# Net510.net
KiCad netlist of a schematic drawn in Altium Designer
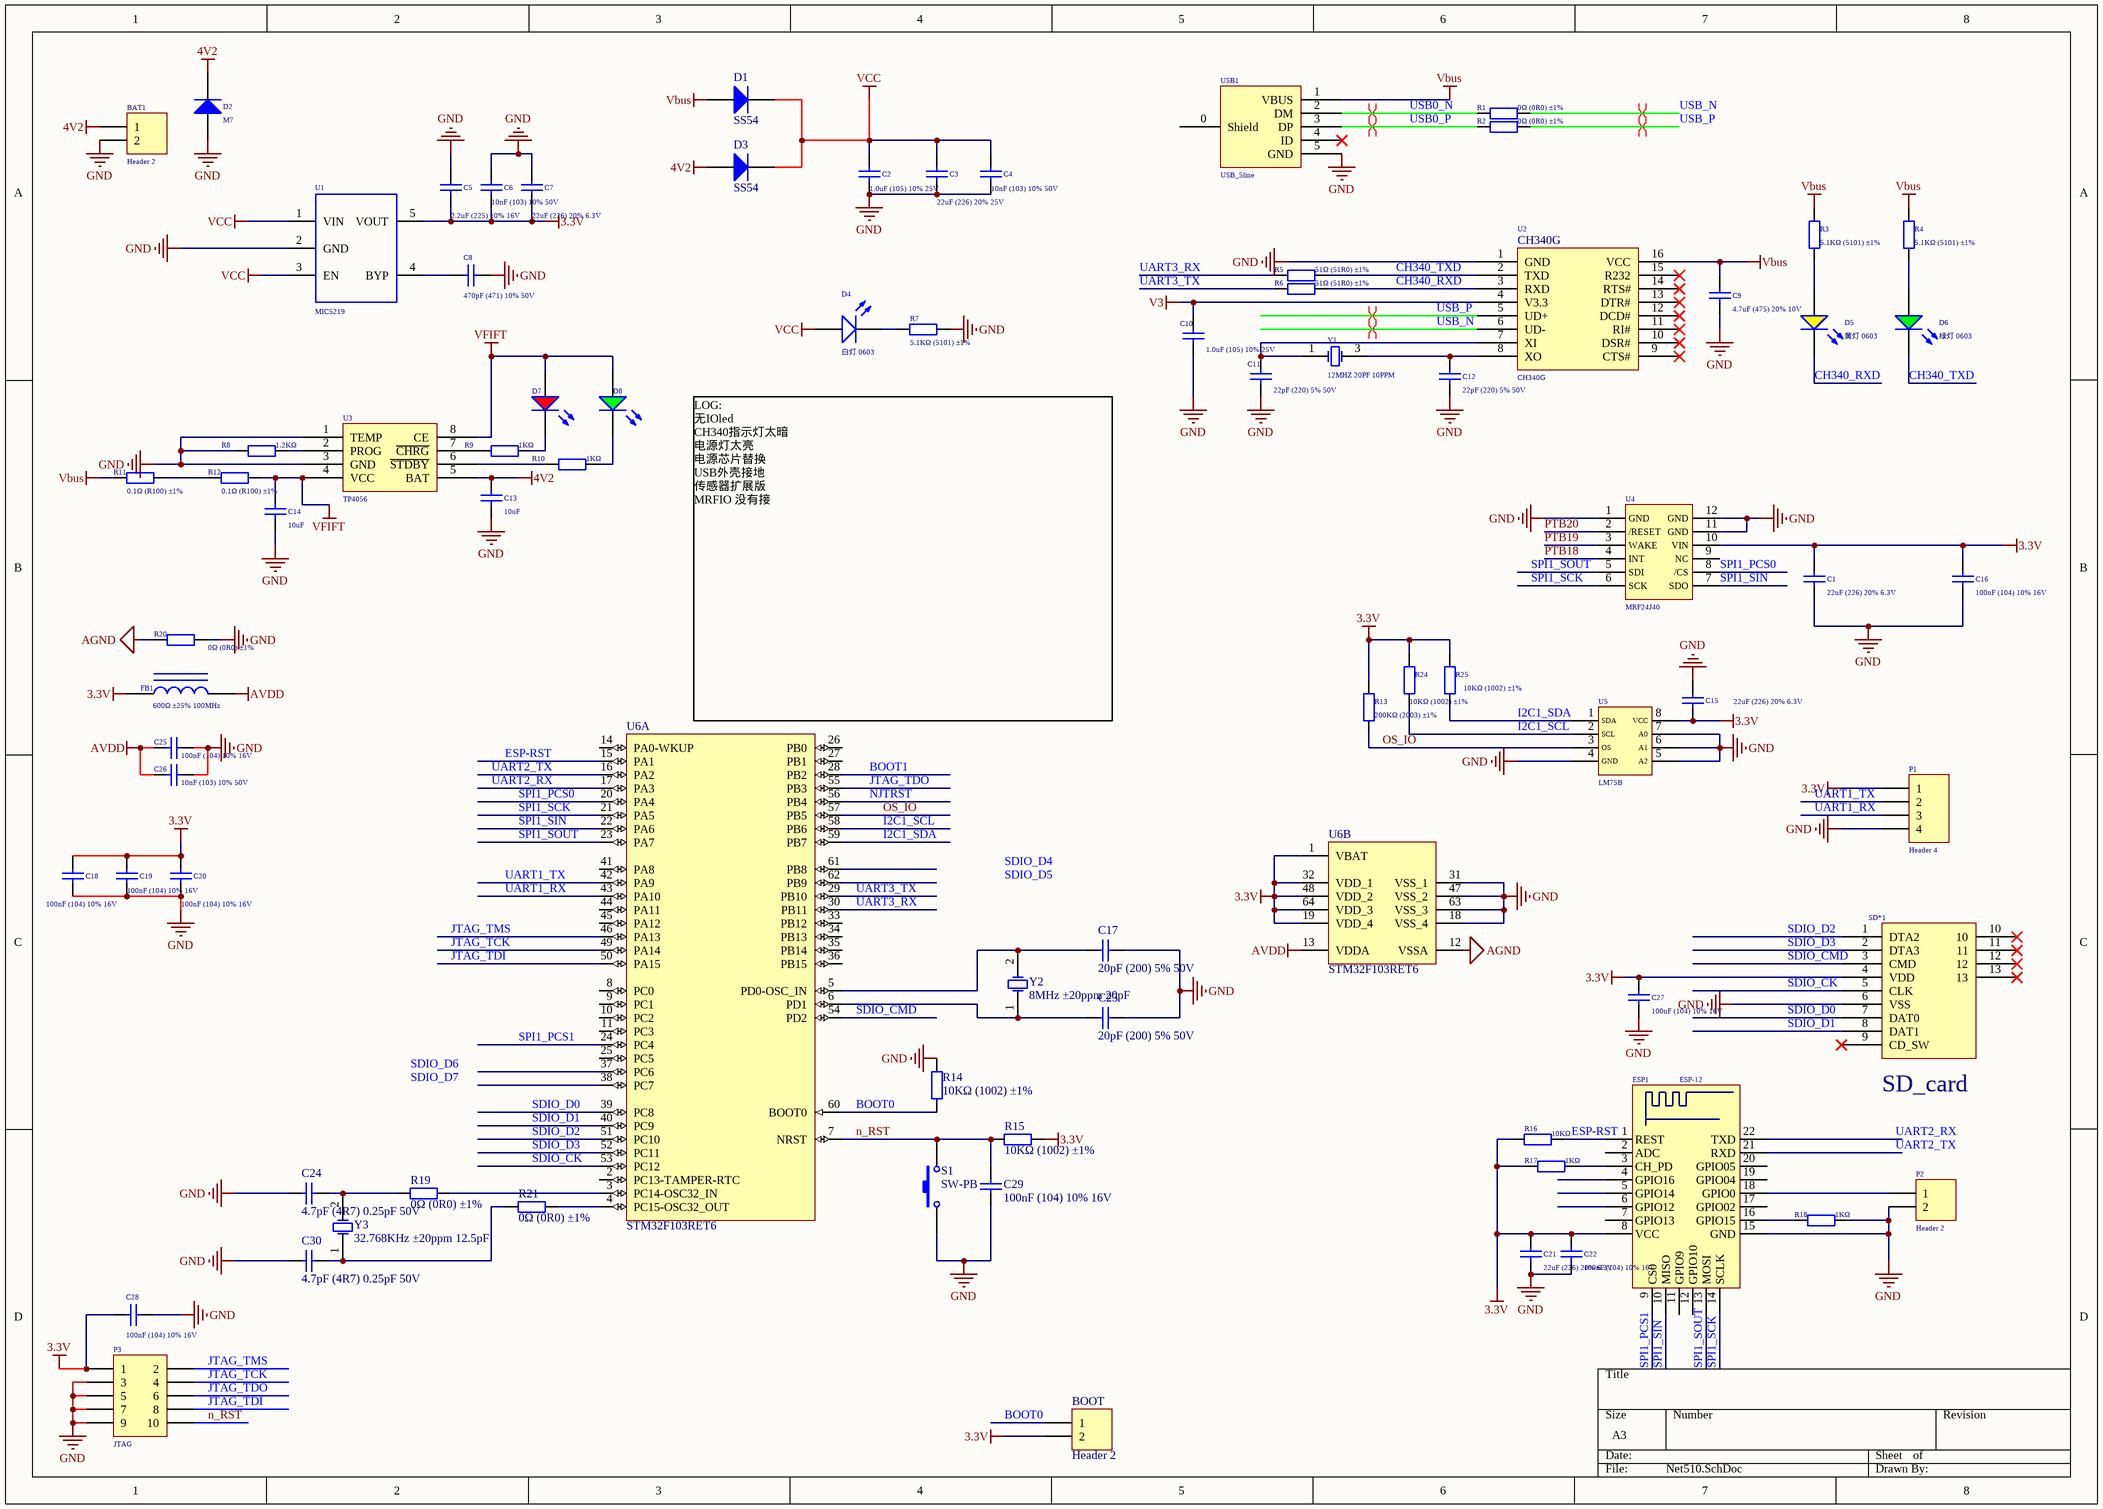
[diagram p0: Net510.SchDoc]

(export (version "E")
  (design (tool "Eeschema 10.0.6"))
  (components
    (comp (ref "BAT1")
      (value "Header 2")
      (footprint "HDR1X2")
      (description "Header, 2-Pin")
      (fields (field (name "PUBLISHER") "Altium Limited"))
      (libsource (lib "Sparks") (part "Header 2"))
    )
    (comp (ref "BOOT")
      (value "Header 2")
      (footprint "HDR1X2")
      (description "Header, 2-Pin")
      (fields (field (name "PUBLISHER") "Altium Limited"))
      (libsource (lib "Sparks") (part "Header 2"))
    )
    (comp (ref "C1")
      (value "22uF (226) 20% 6.3V")
      (footprint "0603_C")
      (description "贴片电容")
      (libsource (lib "Miscellaneous Devices LC") (part "0603 22uF (226) 20% 6.3V"))
    )
    (comp (ref "C2")
      (value "1.0uF (105) 10% 25V")
      (footprint "0402_C")
      (description "贴片电容")
      (libsource (lib "Miscellaneous Devices LC") (part "0402 1.0uF (105) 10% 25V"))
    )
    (comp (ref "C3")
      (value "22uF (226) 20% 25V")
      (footprint "0805_C")
      (description "贴片电容")
      (libsource (lib "Miscellaneous Devices LC") (part "0805 22uF (226) 20% 25V"))
    )
    (comp (ref "C4")
      (value "10nF (103) 10% 50V")
      (footprint "0402_C")
      (description "贴片电容")
      (libsource (lib "Miscellaneous Devices LC") (part "0402 10nF (103) 10% 50V"))
    )
    (comp (ref "C5")
      (value "2.2uF (225) 10% 16V")
      (footprint "0603_C")
      (description "贴片电容")
      (libsource (lib "Miscellaneous Devices LC") (part "0603 2.2uF (225) 10% 16V"))
    )
    (comp (ref "C6")
      (value "10nF (103) 10% 50V")
      (footprint "0402_C")
      (description "贴片电容")
      (libsource (lib "Miscellaneous Devices LC") (part "0402 10nF (103) 10% 50V"))
    )
    (comp (ref "C7")
      (value "22uF (226) 20% 6.3V")
      (footprint "0603_C")
      (description "贴片电容")
      (libsource (lib "Miscellaneous Devices LC") (part "0603 22uF (226) 20% 6.3V"))
    )
    (comp (ref "C8")
      (value "470pF (471) 10% 50V")
      (footprint "0402_C")
      (description "贴片电容")
      (libsource (lib "Miscellaneous Devices LC") (part "0402 470pF (471) 10% 50V"))
    )
    (comp (ref "C9")
      (value "4.7uF (475) 20% 10V")
      (footprint "0402_C")
      (description "贴片电容")
      (libsource (lib "Miscellaneous Devices LC") (part "0402 4.7uF (475) 20% 10V"))
    )
    (comp (ref "C10")
      (value "1.0uF (105) 10% 25V")
      (footprint "0402_C")
      (description "贴片电容")
      (libsource (lib "Miscellaneous Devices LC") (part "0402 1.0uF (105) 10% 25V"))
    )
    (comp (ref "C11")
      (value "22pF (220) 5% 50V")
      (footprint "0402_C")
      (description "贴片电容")
      (libsource (lib "Miscellaneous Devices LC") (part "0402 22pF (220) 5% 50V"))
    )
    (comp (ref "C12")
      (value "22pF (220) 5% 50V")
      (footprint "0402_C")
      (description "贴片电容")
      (libsource (lib "Miscellaneous Devices LC") (part "0402 22pF (220) 5% 50V"))
    )
    (comp (ref "C13")
      (value "10uF")
      (footprint "0402_C")
      (description "贴片电容")
      (libsource (lib "Cap") (part "0402 10uF (106) 20% 6.3V"))
    )
    (comp (ref "C14")
      (value "10uF")
      (footprint "0402_C")
      (description "贴片电容")
      (libsource (lib "Cap") (part "0402 10uF (106) 20% 6.3V"))
    )
    (comp (ref "C15")
      (value "22uF (226) 20% 6.3V")
      (footprint "0603_C")
      (description "贴片电容")
      (libsource (lib "Miscellaneous Devices LC") (part "0603 22uF (226) 20% 6.3V"))
    )
    (comp (ref "C16")
      (value "100nF (104) 10% 16V")
      (footprint "0402_C")
      (description "贴片电容")
      (libsource (lib "Miscellaneous Devices LC") (part "0402 100nF (104) 10% 16V"))
    )
    (comp (ref "C17")
      (value "20pF (200) 5% 50V")
      (footprint "0402_C")
      (description "贴片电容")
      (libsource (lib "Miscellaneous Devices LC") (part "0402 20pF (200) 5% 50V"))
    )
    (comp (ref "C18")
      (value "100nF (104) 10% 16V")
      (footprint "0402_C")
      (description "贴片电容")
      (libsource (lib "Miscellaneous Devices LC") (part "0402 100nF (104) 10% 16V"))
    )
    (comp (ref "C19")
      (value "100nF (104) 10% 16V")
      (footprint "0402_C")
      (description "贴片电容")
      (libsource (lib "Miscellaneous Devices LC") (part "0402 100nF (104) 10% 16V"))
    )
    (comp (ref "C20")
      (value "100nF (104) 10% 16V")
      (footprint "0402_C")
      (description "贴片电容")
      (libsource (lib "Miscellaneous Devices LC") (part "0402 100nF (104) 10% 16V"))
    )
    (comp (ref "C21")
      (value "22uF (226) 20% 6.3V")
      (footprint "0603_C")
      (description "贴片电容")
      (libsource (lib "Miscellaneous Devices LC") (part "0603 22uF (226) 20% 6.3V"))
    )
    (comp (ref "C22")
      (value "100nF (104) 10% 16V")
      (footprint "0402_C")
      (description "贴片电容")
      (libsource (lib "Miscellaneous Devices LC") (part "0402 100nF (104) 10% 16V"))
    )
    (comp (ref "C23")
      (value "20pF (200) 5% 50V")
      (footprint "0402_C")
      (description "贴片电容")
      (libsource (lib "Miscellaneous Devices LC") (part "0402 20pF (200) 5% 50V"))
    )
    (comp (ref "C24")
      (value "4.7pF (4R7) 0.25pF 50V")
      (footprint "0402_C")
      (description "贴片电容")
      (libsource (lib "Miscellaneous Devices LC") (part "0402 4.7pF (4R7) 0.25pF 50V"))
    )
    (comp (ref "C25")
      (value "100nF (104) 10% 16V")
      (footprint "0402_C")
      (description "贴片电容")
      (libsource (lib "Miscellaneous Devices LC") (part "0402 100nF (104) 10% 16V"))
    )
    (comp (ref "C26")
      (value "10nF (103) 10% 50V")
      (footprint "0402_C")
      (description "贴片电容")
      (libsource (lib "Miscellaneous Devices LC") (part "0402 10nF (103) 10% 50V"))
    )
    (comp (ref "C27")
      (value "100nF (104) 10% 16V")
      (footprint "0402_C")
      (description "贴片电容")
      (libsource (lib "Miscellaneous Devices LC") (part "0402 100nF (104) 10% 16V"))
    )
    (comp (ref "C28")
      (value "100nF (104) 10% 16V")
      (footprint "0402_C")
      (description "贴片电容")
      (libsource (lib "Miscellaneous Devices LC") (part "0402 100nF (104) 10% 16V"))
    )
    (comp (ref "C29")
      (value "100nF (104) 10% 16V")
      (footprint "0402_C")
      (description "贴片电容")
      (libsource (lib "Miscellaneous Devices LC") (part "0402 100nF (104) 10% 16V"))
    )
    (comp (ref "C30")
      (value "4.7pF (4R7) 0.25pF 50V")
      (footprint "0402_C")
      (description "贴片电容")
      (libsource (lib "Miscellaneous Devices LC") (part "0402 4.7pF (4R7) 0.25pF 50V"))
    )
    (comp (ref "D1")
      (value "SS54")
      (footprint "SMA(DO-214AC)_S1")
      (description "二极管")
      (libsource (lib "Miscellaneous Devices LC") (part "SMA(DO-214AC) SS54"))
    )
    (comp (ref "D2")
      (value "M7")
      (footprint "SMA(DO-214AC)_S1")
      (description "二极管")
      (libsource (lib "Miscellaneous Devices LC") (part "SMA(DO-214AC) M7"))
    )
    (comp (ref "D3")
      (value "SS54")
      (footprint "SMA(DO-214AC)_S1")
      (description "二极管")
      (libsource (lib "Miscellaneous Devices LC") (part "SMA(DO-214AC) SS54"))
    )
    (comp (ref "D4")
      (value "白灯 0603")
      (footprint "0603_LED_S1")
      (description "发光二极管")
      (libsource (lib "Miscellaneous Devices LC") (part "0603 白灯"))
    )
    (comp (ref "D5")
      (value "黄灯 0603")
      (footprint "0603_LED_S1")
      (description "发光二极管")
      (libsource (lib "Miscellaneous Devices LC") (part "0603 黄灯"))
    )
    (comp (ref "D6")
      (value "绿灯 0603")
      (footprint "0603_LED_S1")
      (description "发光二极管")
      (libsource (lib "Miscellaneous Devices LC") (part "0603 绿灯"))
    )
    (comp (ref "D7")
      (value "红灯 0603")
      (footprint "0603_LED_S1")
      (description "发光二极管")
      (libsource (lib "LED") (part "0603 红灯"))
    )
    (comp (ref "D8")
      (value "绿灯 0603")
      (footprint "0603_LED_S1")
      (description "发光二极管")
      (libsource (lib "LED") (part "0603 绿灯"))
    )
    (comp (ref "ESP1") (value "ESP-12") (footprint "ESP-12") (libsource (lib "2号库") (part "ESP-12")))
    (comp (ref "FB1")
      (value "600Ω ±25% 100MHz")
      (footprint "0805_L")
      (description "贴片磁珠")
      (libsource (lib "Miscellaneous Devices LC") (part "0805 600Ω 25% 100MHz"))
    )
    (comp (ref "P1")
      (value "Header 4")
      (footprint "HDR1X4")
      (description "Header, 4-Pin")
      (fields (field (name "PUBLISHER") "Altium Limited"))
      (libsource (lib "Sparks") (part "Header 4"))
    )
    (comp (ref "P2")
      (value "Header 2")
      (footprint "HDR1X2")
      (description "Header, 2-Pin")
      (fields (field (name "PUBLISHER") "Altium Limited"))
      (libsource (lib "Sparks") (part "Header 2"))
    )
    (comp (ref "P3")
      (value "JTAG")
      (footprint "HDR2X5")
      (description "Header, 5-Pin, Dual row")
      (fields (field (name "PUBLISHER") "Altium Limited"))
      (libsource (lib "Sparks") (part "Header 5X2"))
    )
    (comp (ref "R1")
      (value "0Ω (0R0) ±1%")
      (footprint "0402_R")
      (description "贴片电阻")
      (libsource (lib "Miscellaneous Devices LC") (part "0402 0Ω (0R0) 1%"))
    )
    (comp (ref "R2")
      (value "0Ω (0R0) ±1%")
      (footprint "0402_R")
      (description "贴片电阻")
      (libsource (lib "Miscellaneous Devices LC") (part "0402 0Ω (0R0) 1%"))
    )
    (comp (ref "R3")
      (value "5.1KΩ (5101) ±1%")
      (footprint "0402_R")
      (description "贴片电阻")
      (libsource (lib "Miscellaneous Devices LC") (part "0402 5.1KΩ (5101) 1%"))
    )
    (comp (ref "R4")
      (value "5.1KΩ (5101) ±1%")
      (footprint "0402_R")
      (description "贴片电阻")
      (libsource (lib "Miscellaneous Devices LC") (part "0402 5.1KΩ (5101) 1%"))
    )
    (comp (ref "R5")
      (value "51Ω (51R0) ±1%")
      (footprint "0402_R")
      (description "贴片电阻")
      (libsource (lib "Miscellaneous Devices LC") (part "0402 51Ω (51R0) 1%"))
    )
    (comp (ref "R6")
      (value "51Ω (51R0) ±1%")
      (footprint "0402_R")
      (description "贴片电阻")
      (libsource (lib "Miscellaneous Devices LC") (part "0402 51Ω (51R0) 1%"))
    )
    (comp (ref "R7")
      (value "5.1KΩ (5101) ±1%")
      (footprint "0402_R")
      (description "贴片电阻")
      (libsource (lib "") (part "0402 5.1KΩ (5101) 1%_1"))
    )
    (comp (ref "R8")
      (value "1.2KΩ")
      (footprint "0402_R")
      (description "贴片电阻")
      (libsource (lib "RES") (part "0402 1.2KΩ (1201) 1%"))
    )
    (comp (ref "R9")
      (value "1KΩ")
      (footprint "0402_R")
      (description "贴片电阻")
      (libsource (lib "RES") (part "0402 1KΩ (1001) 1%"))
    )
    (comp (ref "R10")
      (value "1KΩ")
      (footprint "0402_R")
      (description "贴片电阻")
      (libsource (lib "RES") (part "0402 1KΩ (1001) 1%"))
    )
    (comp (ref "R11")
      (value "0.1Ω (R100) ±1%")
      (footprint "1206_R")
      (description "贴片电阻")
      (libsource (lib "Miscellaneous Devices LC") (part "1206 0.1Ω (R100) 1%"))
    )
    (comp (ref "R12")
      (value "0.1Ω (R100) ±1%")
      (footprint "1206_R")
      (description "贴片电阻")
      (libsource (lib "Miscellaneous Devices LC") (part "1206 0.1Ω (R100) 1%"))
    )
    (comp (ref "R13")
      (value "200KΩ (2003) ±1%")
      (footprint "0402_R")
      (description "贴片电阻")
      (libsource (lib "Miscellaneous Devices LC") (part "0402 200KΩ (2003) 1%"))
    )
    (comp (ref "R14")
      (value "10KΩ (1002) ±1%")
      (footprint "0402_R")
      (description "贴片电阻")
      (libsource (lib "Miscellaneous Devices LC") (part "0402 10KΩ (1002) 1%"))
    )
    (comp (ref "R15")
      (value "10KΩ (1002) ±1%")
      (footprint "0402_R")
      (description "贴片电阻")
      (libsource (lib "") (part "0402 10KΩ (1002) 1%_1"))
    )
    (comp (ref "R16")
      (value "10KΩ")
      (footprint "0603_R")
      (description "贴片电阻")
      (libsource (lib "RES") (part "0603 10KΩ (1002) 1%"))
    )
    (comp (ref "R17")
      (value "1KΩ")
      (footprint "0603_R")
      (description "贴片电阻")
      (libsource (lib "RES") (part "0603 1KΩ (1001) 1%"))
    )
    (comp (ref "R18")
      (value "1KΩ")
      (footprint "0603_R")
      (description "贴片电阻")
      (libsource (lib "RES") (part "0603 1KΩ (1001) 1%"))
    )
    (comp (ref "R19")
      (value "0Ω (0R0) ±1%")
      (footprint "0402_R")
      (description "贴片电阻")
      (libsource (lib "Miscellaneous Devices LC") (part "0402 0Ω (0R0) 1%"))
    )
    (comp (ref "R20")
      (value "0Ω (0R0) ±1%")
      (footprint "0402_R")
      (description "贴片电阻")
      (libsource (lib "Miscellaneous Devices LC") (part "0402 0Ω (0R0) 1%"))
    )
    (comp (ref "R21")
      (value "0Ω (0R0) ±1%")
      (footprint "0402_R")
      (description "贴片电阻")
      (libsource (lib "Miscellaneous Devices LC") (part "0402 0Ω (0R0) 1%"))
    )
    (comp (ref "R24")
      (value "10KΩ (1002) ±1%")
      (footprint "0402_R")
      (description "贴片电阻")
      (libsource (lib "Miscellaneous Devices LC") (part "0402 10KΩ (1002) 1%"))
    )
    (comp (ref "R25")
      (value "10KΩ (1002) ±1%")
      (footprint "0402_R")
      (description "贴片电阻")
      (libsource (lib "Miscellaneous Devices LC") (part "0402 10KΩ (1002) 1%"))
    )
    (comp (ref "S1")
      (value "SW-PB")
      (footprint "key 3*4*2")
      (description "Switch")
      (fields (field (name "PUBLISHER") "Altium Limited"))
      (libsource (lib "Miscellaneous Devices") (part "SW-PB"))
    )
    (comp (ref "SD*1") (value "TF_card") (footprint "TF卡座(短体)") (libsource (lib "2号库") (part "TF_card")))
    (comp (ref "U1")
      (value "MIC5219")
      (footprint "SOT-23-5")
      (description "LDO")
      (libsource (lib "K60-V4.0") (part "MIC5219"))
    )
    (comp (ref "U2")
      (value "CH340G")
      (footprint "SOIC-16_150mil")
      (description "USB")
      (libsource (lib "Miscellaneous Devices LC") (part "CH340G_[C14267]"))
    )
    (comp (ref "U3")
      (value "TP4056")
      (footprint "SOP-8_EP_150mil")
      (description "电池电源管理")
      (libsource (lib "IC") (part "TP4056_[C16581]"))
    )
    (comp (ref "U4") (value "MRF24J40") (footprint "MRF24J40") (libsource (lib "2号库") (part "MRF24J40")))
    (comp (ref "U5")
      (value "LM75B")
      (footprint "LC-SOIC-8_150mil")
      (libsource (lib "jlcUser") (part "LM75B"))
    )
    (comp (ref "U6")
      (value "STM32F103RET6")
      (footprint "LQFP-64_10x10x05P")
      (description "ARM")
      (libsource (lib "Miscellaneous Devices LC") (part "STM32F103RET6"))
    )
    (comp (ref "USB1")
      (value "USB_5line")
      (footprint "USB-MICRO-5P-2F")
      (libsource (lib "2号库") (part "USB_5line"))
    )
    (comp (ref "Y1")
      (value "12MHZ 20PF 10PPM")
      (footprint "SMD-3225_4P")
      (description "贴片晶振")
      (libsource (lib "Miscellaneous Devices LC") (part "SMD-3225_4P  12MHZ 20PF 10PPM"))
    )
    (comp (ref "Y2")
      (value "8MHz ±20ppm 20pF")
      (footprint "SMD-5032_2P")
      (description "贴片晶振")
      (libsource (lib "Miscellaneous Devices LC") (part "SMD-5032_2P 8MHz 20ppm 20pF"))
    )
    (comp (ref "Y3")
      (value "32.768KHz ±20ppm 12.5pF")
      (footprint "SMD-3215_2P FC - 135")
      (description "贴片晶振")
      (libsource (lib "Miscellaneous Devices LC") (part "SMD-3215_2P 32.768KHz 20ppm 12.5pF"))
    )
  )
  (nets
    (net (code "1") (name "/BOOT0") (class "Default")
      (node (ref "BOOT") (pin "1") (pinfunction "1_1") (pintype "passive"))
      (node (ref "R14") (pin "1") (pinfunction "1_1") (pintype "passive"))
      (node (ref "U6") (pin "60") (pinfunction "BOOT0_60") (pintype "input"))
    )
    (net (code "2") (name "/BOOT1") (class "Default")
      (node (ref "U6") (pin "28") (pinfunction "PB2_28") (pintype "bidirectional"))
    )
    (net (code "3") (name "/CH340_RXD") (class "Default")
      (node (ref "D5") (pin "K") (pinfunction "K_K") (pintype "passive"))
      (node (ref "R6") (pin "2") (pinfunction "2_2") (pintype "passive"))
      (node (ref "U2") (pin "3") (pinfunction "RXD_3") (pintype "passive"))
    )
    (net (code "4") (name "/CH340_TXD") (class "Default")
      (node (ref "D6") (pin "K") (pinfunction "K_K") (pintype "passive"))
      (node (ref "R5") (pin "2") (pinfunction "2_2") (pintype "passive"))
      (node (ref "U2") (pin "2") (pinfunction "TXD_2") (pintype "passive"))
    )
    (net (code "5") (name "/ESP-RST") (class "Default")
      (node (ref "ESP1") (pin "1") (pinfunction "REST_1") (pintype "passive"))
      (node (ref "R16") (pin "2") (pinfunction "2_2") (pintype "passive"))
      (node (ref "U6") (pin "15") (pinfunction "PA1_15") (pintype "bidirectional"))
    )
    (net (code "6") (name "/I2C1_SCL") (class "Default")
      (node (ref "R24") (pin "1") (pinfunction "1_1") (pintype "passive"))
      (node (ref "U5") (pin "2") (pinfunction "SCL_2") (pintype "passive"))
      (node (ref "U6") (pin "58") (pinfunction "PB6_58") (pintype "bidirectional"))
    )
    (net (code "7") (name "/I2C1_SDA") (class "Default")
      (node (ref "R25") (pin "1") (pinfunction "1_1") (pintype "passive"))
      (node (ref "U5") (pin "1") (pinfunction "SDA_1") (pintype "passive"))
      (node (ref "U6") (pin "59") (pinfunction "PB7_59") (pintype "bidirectional"))
    )
    (net (code "8") (name "/JTAG_TCK") (class "Default")
      (node (ref "P3") (pin "4") (pinfunction "4_4") (pintype "passive"))
      (node (ref "U6") (pin "49") (pinfunction "PA14_49") (pintype "bidirectional"))
    )
    (net (code "9") (name "/JTAG_TDI") (class "Default")
      (node (ref "P3") (pin "8") (pinfunction "8_8") (pintype "passive"))
      (node (ref "U6") (pin "50") (pinfunction "PA15_50") (pintype "bidirectional"))
    )
    (net (code "10") (name "/JTAG_TDO") (class "Default")
      (node (ref "P3") (pin "6") (pinfunction "6_6") (pintype "passive"))
      (node (ref "U6") (pin "55") (pinfunction "PB3_55") (pintype "bidirectional"))
    )
    (net (code "11") (name "/JTAG_TMS") (class "Default")
      (node (ref "P3") (pin "2") (pinfunction "2_2") (pintype "passive"))
      (node (ref "U6") (pin "46") (pinfunction "PA13_46") (pintype "bidirectional"))
    )
    (net (code "12") (name "/NJTRST") (class "Default")
      (node (ref "U6") (pin "56") (pinfunction "PB4_56") (pintype "bidirectional"))
    )
    (net (code "13") (name "/OS_IO") (class "Default")
      (node (ref "R13") (pin "1") (pinfunction "1_1") (pintype "passive"))
      (node (ref "U5") (pin "3") (pinfunction "OS_3") (pintype "passive"))
      (node (ref "U6") (pin "57") (pinfunction "PB5_57") (pintype "bidirectional"))
    )
    (net (code "14") (name "/PTB18") (class "Default")
      (node (ref "U4") (pin "4") (pinfunction "INT_4") (pintype "passive"))
    )
    (net (code "15") (name "/PTB19") (class "Default")
      (node (ref "U4") (pin "3") (pinfunction "WAKE_3") (pintype "passive"))
    )
    (net (code "16") (name "/PTB20") (class "Default")
      (node (ref "U4") (pin "2") (pinfunction "/RESET_2") (pintype "passive"))
    )
    (net (code "17") (name "/SDIO_CK") (class "Default")
      (node (ref "SD*1") (pin "5") (pinfunction "CLK_5") (pintype "passive"))
      (node (ref "U6") (pin "53") (pinfunction "PC12_53") (pintype "bidirectional"))
    )
    (net (code "18") (name "/SDIO_CMD") (class "Default")
      (node (ref "SD*1") (pin "3") (pinfunction "CMD_3") (pintype "passive"))
      (node (ref "U6") (pin "54") (pinfunction "PD2_54") (pintype "bidirectional"))
    )
    (net (code "19") (name "/SDIO_D0") (class "Default")
      (node (ref "SD*1") (pin "7") (pinfunction "DAT0_7") (pintype "passive"))
      (node (ref "U6") (pin "39") (pinfunction "PC8_39") (pintype "bidirectional"))
    )
    (net (code "20") (name "/SDIO_D1") (class "Default")
      (node (ref "SD*1") (pin "8") (pinfunction "DAT1_8") (pintype "passive"))
      (node (ref "U6") (pin "40") (pinfunction "PC9_40") (pintype "bidirectional"))
    )
    (net (code "21") (name "/SDIO_D2") (class "Default")
      (node (ref "SD*1") (pin "1") (pinfunction "DTA2_1") (pintype "passive"))
      (node (ref "U6") (pin "51") (pinfunction "PC10_51") (pintype "bidirectional"))
    )
    (net (code "22") (name "/SDIO_D3") (class "Default")
      (node (ref "SD*1") (pin "2") (pinfunction "DTA3_2") (pintype "passive"))
      (node (ref "U6") (pin "52") (pinfunction "PC11_52") (pintype "bidirectional"))
    )
    (net (code "27") (name "/SPI1_PCS0") (class "Default")
      (node (ref "U4") (pin "8") (pinfunction "/CS_8") (pintype "passive"))
      (node (ref "U6") (pin "20") (pinfunction "PA4_20") (pintype "bidirectional"))
    )
    (net (code "28") (name "/SPI1_PCS1") (class "Default")
      (node (ref "ESP1") (pin "9") (pinfunction "CS0_9") (pintype "passive"))
      (node (ref "U6") (pin "24") (pinfunction "PC4_24") (pintype "bidirectional"))
    )
    (net (code "29") (name "/SPI1_SCK") (class "Default")
      (node (ref "ESP1") (pin "14") (pinfunction "SCLK_14") (pintype "passive"))
      (node (ref "U4") (pin "6") (pinfunction "SCK_6") (pintype "passive"))
      (node (ref "U6") (pin "21") (pinfunction "PA5_21") (pintype "bidirectional"))
    )
    (net (code "30") (name "/SPI1_SIN") (class "Default")
      (node (ref "ESP1") (pin "10") (pinfunction "MISO_10") (pintype "passive"))
      (node (ref "U4") (pin "7") (pinfunction "SDO_7") (pintype "passive"))
      (node (ref "U6") (pin "22") (pinfunction "PA6_22") (pintype "bidirectional"))
    )
    (net (code "31") (name "/SPI1_SOUT") (class "Default")
      (node (ref "ESP1") (pin "13") (pinfunction "MOSI_13") (pintype "passive"))
      (node (ref "U4") (pin "5") (pinfunction "SDI_5") (pintype "passive"))
      (node (ref "U6") (pin "23") (pinfunction "PA7_23") (pintype "bidirectional"))
    )
    (net (code "32") (name "/UART1_RX") (class "Default")
      (node (ref "P1") (pin "3") (pinfunction "3_3") (pintype "passive"))
      (node (ref "U6") (pin "43") (pinfunction "PA10_43") (pintype "bidirectional"))
    )
    (net (code "33") (name "/UART1_TX") (class "Default")
      (node (ref "P1") (pin "2") (pinfunction "2_2") (pintype "passive"))
      (node (ref "U6") (pin "42") (pinfunction "PA9_42") (pintype "bidirectional"))
    )
    (net (code "34") (name "/UART2_RX") (class "Default")
      (node (ref "ESP1") (pin "22") (pinfunction "TXD_22") (pintype "passive"))
      (node (ref "U6") (pin "17") (pinfunction "PA3_17") (pintype "bidirectional"))
    )
    (net (code "35") (name "/UART2_TX") (class "Default")
      (node (ref "ESP1") (pin "21") (pinfunction "RXD_21") (pintype "passive"))
      (node (ref "U6") (pin "16") (pinfunction "PA2_16") (pintype "bidirectional"))
    )
    (net (code "36") (name "/UART3_RX") (class "Default")
      (node (ref "R5") (pin "1") (pinfunction "1_1") (pintype "passive"))
      (node (ref "U6") (pin "30") (pinfunction "PB11_30") (pintype "bidirectional"))
    )
    (net (code "37") (name "/UART3_TX") (class "Default")
      (node (ref "R6") (pin "1") (pinfunction "1_1") (pintype "passive"))
      (node (ref "U6") (pin "29") (pinfunction "PB10_29") (pintype "bidirectional"))
    )
    (net (code "38") (name "/USB0_N") (class "Default")
      (node (ref "R1") (pin "1") (pinfunction "1_1") (pintype "passive"))
      (node (ref "USB1") (pin "2") (pinfunction "DM_2") (pintype "passive"))
    )
    (net (code "39") (name "/USB0_P") (class "Default")
      (node (ref "R2") (pin "1") (pinfunction "1_1") (pintype "passive"))
      (node (ref "USB1") (pin "3") (pinfunction "DP_3") (pintype "passive"))
    )
    (net (code "40") (name "/USB_N") (class "Default")
      (node (ref "R1") (pin "2") (pinfunction "2_2") (pintype "passive"))
      (node (ref "U2") (pin "6") (pinfunction "UD-_6") (pintype "passive"))
    )
    (net (code "41") (name "/USB_P") (class "Default")
      (node (ref "R2") (pin "2") (pinfunction "2_2") (pintype "passive"))
      (node (ref "U2") (pin "5") (pinfunction "UD+_5") (pintype "passive"))
    )
    (net (code "42") (name "/n_RST") (class "Default")
      (node (ref "C29") (pin "2") (pinfunction "2_2") (pintype "passive"))
      (node (ref "P3") (pin "10") (pinfunction "10_10") (pintype "passive"))
      (node (ref "R15") (pin "2") (pinfunction "2_2") (pintype "passive"))
      (node (ref "S1") (pin "2") (pinfunction "2_2") (pintype "passive"))
      (node (ref "U6") (pin "7") (pinfunction "NRST_7") (pintype "bidirectional"))
    )
    (net (code "43") (name "3.3V") (class "Default")
      (node (ref "BOOT") (pin "2") (pinfunction "2_2") (pintype "passive"))
      (node (ref "C1") (pin "2") (pinfunction "2_2") (pintype "passive"))
      (node (ref "C15") (pin "1") (pinfunction "1_1") (pintype "passive"))
      (node (ref "C16") (pin "2") (pinfunction "2_2") (pintype "passive"))
      (node (ref "C18") (pin "2") (pinfunction "2_2") (pintype "passive"))
      (node (ref "C19") (pin "2") (pinfunction "2_2") (pintype "passive"))
      (node (ref "C20") (pin "2") (pinfunction "2_2") (pintype "passive"))
      (node (ref "C21") (pin "2") (pinfunction "2_2") (pintype "passive"))
      (node (ref "C22") (pin "2") (pinfunction "2_2") (pintype "passive"))
      (node (ref "C27") (pin "2") (pinfunction "2_2") (pintype "passive"))
      (node (ref "C28") (pin "1") (pinfunction "1_1") (pintype "passive"))
      (node (ref "C5") (pin "1") (pinfunction "1_1") (pintype "passive"))
      (node (ref "C6") (pin "1") (pinfunction "1_1") (pintype "passive"))
      (node (ref "C7") (pin "1") (pinfunction "1_1") (pintype "passive"))
      (node (ref "ESP1") (pin "8") (pinfunction "VCC_8") (pintype "passive"))
      (node (ref "FB1") (pin "1") (pinfunction "1_1") (pintype "passive"))
      (node (ref "P1") (pin "1") (pinfunction "1_1") (pintype "passive"))
      (node (ref "P3") (pin "1") (pinfunction "1_1") (pintype "passive"))
      (node (ref "R13") (pin "2") (pinfunction "2_2") (pintype "passive"))
      (node (ref "R15") (pin "1") (pinfunction "1_1") (pintype "passive"))
      (node (ref "R16") (pin "1") (pinfunction "1_1") (pintype "passive"))
      (node (ref "R17") (pin "1") (pinfunction "1_1") (pintype "passive"))
      (node (ref "R24") (pin "2") (pinfunction "2_2") (pintype "passive"))
      (node (ref "R25") (pin "2") (pinfunction "2_2") (pintype "passive"))
      (node (ref "SD*1") (pin "4") (pinfunction "VDD_4") (pintype "passive"))
      (node (ref "U1") (pin "5") (pinfunction "VOUT_5") (pintype "passive"))
      (node (ref "U4") (pin "10") (pinfunction "VIN_10") (pintype "passive"))
      (node (ref "U5") (pin "8") (pinfunction "VCC_8") (pintype "passive"))
      (node (ref "U6") (pin "1") (pinfunction "VBAT_1") (pintype "power_in"))
      (node (ref "U6") (pin "19") (pinfunction "VDD_4_19") (pintype "power_in"))
      (node (ref "U6") (pin "32") (pinfunction "VDD_1_32") (pintype "power_in"))
      (node (ref "U6") (pin "48") (pinfunction "VDD_2_48") (pintype "power_in"))
      (node (ref "U6") (pin "64") (pinfunction "VDD_3_64") (pintype "power_in"))
    )
    (net (code "44") (name "4V2") (class "Default")
      (node (ref "BAT1") (pin "1") (pinfunction "1_1") (pintype "passive"))
      (node (ref "C13") (pin "2") (pinfunction "2_2") (pintype "passive"))
      (node (ref "D2") (pin "2") (pinfunction "K_2") (pintype "passive"))
      (node (ref "D3") (pin "1") (pinfunction "A_1") (pintype "passive"))
      (node (ref "U3") (pin "5") (pinfunction "BAT_5") (pintype "passive"))
    )
    (net (code "45") (name "AGND") (class "Default")
      (node (ref "R20") (pin "1") (pinfunction "1_1") (pintype "passive"))
      (node (ref "U6") (pin "12") (pinfunction "VSSA_12") (pintype "power_in"))
    )
    (net (code "46") (name "AVDD") (class "Default")
      (node (ref "C25") (pin "1") (pinfunction "1_1") (pintype "passive"))
      (node (ref "C26") (pin "1") (pinfunction "1_1") (pintype "passive"))
      (node (ref "FB1") (pin "2") (pinfunction "2_2") (pintype "passive"))
      (node (ref "U6") (pin "13") (pinfunction "VDDA_13") (pintype "power_in"))
    )
    (net (code "47") (name "GND") (class "Default")
      (node (ref "BAT1") (pin "2") (pinfunction "2_2") (pintype "passive"))
      (node (ref "C1") (pin "1") (pinfunction "1_1") (pintype "passive"))
      (node (ref "C10") (pin "1") (pinfunction "1_1") (pintype "passive"))
      (node (ref "C11") (pin "1") (pinfunction "1_1") (pintype "passive"))
      (node (ref "C12") (pin "1") (pinfunction "1_1") (pintype "passive"))
      (node (ref "C13") (pin "1") (pinfunction "1_1") (pintype "passive"))
      (node (ref "C14") (pin "1") (pinfunction "1_1") (pintype "passive"))
      (node (ref "C15") (pin "2") (pinfunction "2_2") (pintype "passive"))
      (node (ref "C16") (pin "1") (pinfunction "1_1") (pintype "passive"))
      (node (ref "C17") (pin "1") (pinfunction "1_1") (pintype "passive"))
      (node (ref "C18") (pin "1") (pinfunction "1_1") (pintype "passive"))
      (node (ref "C19") (pin "1") (pinfunction "1_1") (pintype "passive"))
      (node (ref "C2") (pin "1") (pinfunction "1_1") (pintype "passive"))
      (node (ref "C20") (pin "1") (pinfunction "1_1") (pintype "passive"))
      (node (ref "C21") (pin "1") (pinfunction "1_1") (pintype "passive"))
      (node (ref "C22") (pin "1") (pinfunction "1_1") (pintype "passive"))
      (node (ref "C23") (pin "1") (pinfunction "1_1") (pintype "passive"))
      (node (ref "C24") (pin "1") (pinfunction "1_1") (pintype "passive"))
      (node (ref "C25") (pin "2") (pinfunction "2_2") (pintype "passive"))
      (node (ref "C26") (pin "2") (pinfunction "2_2") (pintype "passive"))
      (node (ref "C27") (pin "1") (pinfunction "1_1") (pintype "passive"))
      (node (ref "C28") (pin "2") (pinfunction "2_2") (pintype "passive"))
      (node (ref "C29") (pin "1") (pinfunction "1_1") (pintype "passive"))
      (node (ref "C3") (pin "1") (pinfunction "1_1") (pintype "passive"))
      (node (ref "C30") (pin "1") (pinfunction "1_1") (pintype "passive"))
      (node (ref "C4") (pin "1") (pinfunction "1_1") (pintype "passive"))
      (node (ref "C5") (pin "2") (pinfunction "2_2") (pintype "passive"))
      (node (ref "C6") (pin "2") (pinfunction "2_2") (pintype "passive"))
      (node (ref "C7") (pin "2") (pinfunction "2_2") (pintype "passive"))
      (node (ref "C8") (pin "2") (pinfunction "2_2") (pintype "passive"))
      (node (ref "C9") (pin "1") (pinfunction "1_1") (pintype "passive"))
      (node (ref "D2") (pin "1") (pinfunction "A_1") (pintype "passive"))
      (node (ref "ESP1") (pin "15") (pinfunction "GND_15") (pintype "passive"))
      (node (ref "P1") (pin "4") (pinfunction "4_4") (pintype "passive"))
      (node (ref "P2") (pin "2") (pinfunction "2_2") (pintype "passive"))
      (node (ref "P3") (pin "3") (pinfunction "3_3") (pintype "passive"))
      (node (ref "P3") (pin "5") (pinfunction "5_5") (pintype "passive"))
      (node (ref "P3") (pin "7") (pinfunction "7_7") (pintype "passive"))
      (node (ref "P3") (pin "9") (pinfunction "9_9") (pintype "passive"))
      (node (ref "R14") (pin "2") (pinfunction "2_2") (pintype "passive"))
      (node (ref "R18") (pin "2") (pinfunction "2_2") (pintype "passive"))
      (node (ref "R20") (pin "2") (pinfunction "2_2") (pintype "passive"))
      (node (ref "R7") (pin "2") (pinfunction "2_2") (pintype "passive"))
      (node (ref "R8") (pin "1") (pinfunction "1_1") (pintype "passive"))
      (node (ref "S1") (pin "1") (pinfunction "1_1") (pintype "passive"))
      (node (ref "SD*1") (pin "6") (pinfunction "VSS_6") (pintype "passive"))
      (node (ref "U1") (pin "2") (pinfunction "GND_2") (pintype "passive"))
      (node (ref "U2") (pin "1") (pinfunction "GND_1") (pintype "passive"))
      (node (ref "U3") (pin "1") (pinfunction "TEMP_1") (pintype "passive"))
      (node (ref "U3") (pin "3") (pinfunction "GND_3") (pintype "passive"))
      (node (ref "U4") (pin "1") (pinfunction "GND_1") (pintype "passive"))
      (node (ref "U4") (pin "11") (pinfunction "GND_11") (pintype "passive"))
      (node (ref "U4") (pin "12") (pinfunction "GND_12") (pintype "passive"))
      (node (ref "U5") (pin "4") (pinfunction "GND_4") (pintype "passive"))
      (node (ref "U5") (pin "5") (pinfunction "A2_5") (pintype "passive"))
      (node (ref "U5") (pin "6") (pinfunction "A1_6") (pintype "passive"))
      (node (ref "U5") (pin "7") (pinfunction "A0_7") (pintype "passive"))
      (node (ref "U6") (pin "18") (pinfunction "VSS_4_18") (pintype "power_in"))
      (node (ref "U6") (pin "31") (pinfunction "VSS_1_31") (pintype "power_in"))
      (node (ref "U6") (pin "47") (pinfunction "VSS_2_47") (pintype "power_in"))
      (node (ref "U6") (pin "63") (pinfunction "VSS_3_63") (pintype "power_in"))
      (node (ref "USB1") (pin "5") (pinfunction "GND_5") (pintype "passive"))
    )
    (net (code "48") (name "Net-(D4-PadK)") (class "Default")
      (node (ref "D4") (pin "K") (pinfunction "K_K") (pintype "passive"))
      (node (ref "R7") (pin "1") (pinfunction "1_1") (pintype "passive"))
    )
    (net (code "49") (name "Net-(D5-PadA)") (class "Default")
      (node (ref "D5") (pin "A") (pinfunction "A_A") (pintype "passive"))
      (node (ref "R3") (pin "1") (pinfunction "1_1") (pintype "passive"))
    )
    (net (code "50") (name "Net-(D6-PadA)") (class "Default")
      (node (ref "D6") (pin "A") (pinfunction "A_A") (pintype "passive"))
      (node (ref "R4") (pin "1") (pinfunction "1_1") (pintype "passive"))
    )
    (net (code "51") (name "Net-(D7-PadK)") (class "Default")
      (node (ref "D7") (pin "K") (pinfunction "K_K") (pintype "passive"))
      (node (ref "R9") (pin "2") (pinfunction "2_2") (pintype "passive"))
    )
    (net (code "52") (name "Net-(D8-PadK)") (class "Default")
      (node (ref "D8") (pin "K") (pinfunction "K_K") (pintype "passive"))
      (node (ref "R10") (pin "2") (pinfunction "2_2") (pintype "passive"))
    )
    (net (code "53") (name "Net-(ESP1-CH_PD)") (class "Default")
      (node (ref "ESP1") (pin "3") (pinfunction "CH_PD_3") (pintype "passive"))
      (node (ref "R17") (pin "2") (pinfunction "2_2") (pintype "passive"))
    )
    (net (code "54") (name "Net-(ESP1-GPIO0)") (class "Default")
      (node (ref "ESP1") (pin "18") (pinfunction "GPIO0_18") (pintype "passive"))
      (node (ref "P2") (pin "1") (pinfunction "1_1") (pintype "passive"))
    )
    (net (code "55") (name "Net-(ESP1-GPIO15)") (class "Default")
      (node (ref "ESP1") (pin "16") (pinfunction "GPIO15_16") (pintype "passive"))
      (node (ref "R18") (pin "1") (pinfunction "1_1") (pintype "passive"))
    )
    (net (code "56") (name "Net-(R11-Pad2)") (class "Default")
      (node (ref "R11") (pin "2") (pinfunction "2_2") (pintype "passive"))
      (node (ref "R12") (pin "1") (pinfunction "1_1") (pintype "passive"))
    )
    (net (code "57") (name "Net-(U1-BYP)") (class "Default")
      (node (ref "C8") (pin "1") (pinfunction "1_1") (pintype "passive"))
      (node (ref "U1") (pin "4") (pinfunction "BYP_4") (pintype "passive"))
    )
    (net (code "58") (name "Net-(U2-XI)") (class "Default")
      (node (ref "C11") (pin "2") (pinfunction "2_2") (pintype "passive"))
      (node (ref "U2") (pin "7") (pinfunction "XI_7") (pintype "passive"))
      (node (ref "Y1") (pin "1") (pinfunction "OSC1_1") (pintype "passive"))
    )
    (net (code "59") (name "Net-(U2-XO)") (class "Default")
      (node (ref "C12") (pin "2") (pinfunction "2_2") (pintype "passive"))
      (node (ref "U2") (pin "8") (pinfunction "XO_8") (pintype "passive"))
      (node (ref "Y1") (pin "3") (pinfunction "OSC2_3") (pintype "passive"))
    )
    (net (code "60") (name "Net-(U3-PROG)") (class "Default")
      (node (ref "R8") (pin "2") (pinfunction "2_2") (pintype "passive"))
      (node (ref "U3") (pin "2") (pinfunction "PROG_2") (pintype "passive"))
    )
    (net (code "61") (name "Net-(U3-~{CHRG})") (class "Default")
      (node (ref "R9") (pin "1") (pinfunction "1_1") (pintype "passive"))
      (node (ref "U3") (pin "7") (pinfunction "~{CHRG}_7") (pintype "passive"))
    )
    (net (code "62") (name "Net-(U3-~{STDBY})") (class "Default")
      (node (ref "R10") (pin "1") (pinfunction "1_1") (pintype "passive"))
      (node (ref "U3") (pin "6") (pinfunction "~{STDBY}_6") (pintype "passive"))
    )
    (net (code "63") (name "Net-(U6A-PC14-OSC32_IN)") (class "Default")
      (node (ref "R19") (pin "2") (pinfunction "2_2") (pintype "passive"))
      (node (ref "U6") (pin "3") (pinfunction "PC14-OSC32_IN_3") (pintype "bidirectional"))
    )
    (net (code "64") (name "Net-(U6A-PC15-OSC32_OUT)") (class "Default")
      (node (ref "R21") (pin "2") (pinfunction "2_2") (pintype "passive"))
      (node (ref "U6") (pin "4") (pinfunction "PC15-OSC32_OUT_4") (pintype "bidirectional"))
    )
    (net (code "65") (name "Net-(U6A-PD0-OSC_IN)") (class "Default")
      (node (ref "C17") (pin "2") (pinfunction "2_2") (pintype "passive"))
      (node (ref "U6") (pin "5") (pinfunction "PD0-OSC_IN_5") (pintype "bidirectional"))
      (node (ref "Y2") (pin "2") (pinfunction "OSC2_2") (pintype "passive"))
    )
    (net (code "66") (name "Net-(U6A-PD1)") (class "Default")
      (node (ref "C23") (pin "2") (pinfunction "2_2") (pintype "passive"))
      (node (ref "U6") (pin "6") (pinfunction "PD1_6") (pintype "bidirectional"))
      (node (ref "Y2") (pin "1") (pinfunction "OSC1_1") (pintype "passive"))
    )
    (net (code "67") (name "Net-(Y3-OSC1)") (class "Default")
      (node (ref "C30") (pin "2") (pinfunction "2_2") (pintype "passive"))
      (node (ref "R21") (pin "1") (pinfunction "1_1") (pintype "passive"))
      (node (ref "Y3") (pin "1") (pinfunction "OSC1_1") (pintype "passive"))
    )
    (net (code "68") (name "Net-(Y3-OSC2)") (class "Default")
      (node (ref "C24") (pin "2") (pinfunction "2_2") (pintype "passive"))
      (node (ref "R19") (pin "1") (pinfunction "1_1") (pintype "passive"))
      (node (ref "Y3") (pin "2") (pinfunction "OSC2_2") (pintype "passive"))
    )
    (net (code "69") (name "V3") (class "Default")
      (node (ref "C10") (pin "2") (pinfunction "2_2") (pintype "passive"))
      (node (ref "U2") (pin "4") (pinfunction "V3.3_4") (pintype "passive"))
    )
    (net (code "70") (name "VCC") (class "Default")
      (node (ref "C2") (pin "2") (pinfunction "2_2") (pintype "passive"))
      (node (ref "C3") (pin "2") (pinfunction "2_2") (pintype "passive"))
      (node (ref "C4") (pin "2") (pinfunction "2_2") (pintype "passive"))
      (node (ref "D1") (pin "2") (pinfunction "K_2") (pintype "passive"))
      (node (ref "D3") (pin "2") (pinfunction "K_2") (pintype "passive"))
      (node (ref "D4") (pin "A") (pinfunction "A_A") (pintype "passive"))
      (node (ref "U1") (pin "1") (pinfunction "VIN_1") (pintype "passive"))
      (node (ref "U1") (pin "3") (pinfunction "EN_3") (pintype "passive"))
    )
    (net (code "71") (name "VFIFT") (class "Default")
      (node (ref "C14") (pin "2") (pinfunction "2_2") (pintype "passive"))
      (node (ref "D7") (pin "A") (pinfunction "A_A") (pintype "passive"))
      (node (ref "D8") (pin "A") (pinfunction "A_A") (pintype "passive"))
      (node (ref "R12") (pin "2") (pinfunction "2_2") (pintype "passive"))
      (node (ref "U3") (pin "4") (pinfunction "VCC_4") (pintype "passive"))
      (node (ref "U3") (pin "8") (pinfunction "CE_8") (pintype "passive"))
    )
    (net (code "72") (name "Vbus") (class "Default")
      (node (ref "C9") (pin "2") (pinfunction "2_2") (pintype "passive"))
      (node (ref "D1") (pin "1") (pinfunction "A_1") (pintype "passive"))
      (node (ref "R11") (pin "1") (pinfunction "1_1") (pintype "passive"))
      (node (ref "R3") (pin "2") (pinfunction "2_2") (pintype "passive"))
      (node (ref "R4") (pin "2") (pinfunction "2_2") (pintype "passive"))
      (node (ref "U2") (pin "16") (pinfunction "VCC_16") (pintype "passive"))
      (node (ref "USB1") (pin "1") (pinfunction "VBUS_1") (pintype "passive"))
    )
    (net (code "73") (name "unconnected-(ESP1-ADC-Pad2)") (class "Default")
      (node (ref "ESP1") (pin "2") (pinfunction "ADC_2") (pintype "passive"))
    )
    (net (code "74") (name "unconnected-(ESP1-GPIO02-Pad17)") (class "Default")
      (node (ref "ESP1") (pin "17") (pinfunction "GPIO02_17") (pintype "passive"))
    )
    (net (code "75") (name "unconnected-(ESP1-GPIO04-Pad19)") (class "Default")
      (node (ref "ESP1") (pin "19") (pinfunction "GPIO04_19") (pintype "passive"))
    )
    (net (code "76") (name "unconnected-(ESP1-GPIO05-Pad20)") (class "Default")
      (node (ref "ESP1") (pin "20") (pinfunction "GPIO05_20") (pintype "passive"))
    )
    (net (code "77") (name "unconnected-(ESP1-GPIO9-Pad11)") (class "Default")
      (node (ref "ESP1") (pin "11") (pinfunction "GPIO9_11") (pintype "passive"))
    )
    (net (code "78") (name "unconnected-(ESP1-GPIO10-Pad12)") (class "Default")
      (node (ref "ESP1") (pin "12") (pinfunction "GPIO10_12") (pintype "passive"))
    )
    (net (code "79") (name "unconnected-(ESP1-GPIO12-Pad6)") (class "Default")
      (node (ref "ESP1") (pin "6") (pinfunction "GPIO12_6") (pintype "passive"))
    )
    (net (code "80") (name "unconnected-(ESP1-GPIO13-Pad7)") (class "Default")
      (node (ref "ESP1") (pin "7") (pinfunction "GPIO13_7") (pintype "passive"))
    )
    (net (code "81") (name "unconnected-(ESP1-GPIO14-Pad5)") (class "Default")
      (node (ref "ESP1") (pin "5") (pinfunction "GPIO14_5") (pintype "passive"))
    )
    (net (code "82") (name "unconnected-(ESP1-GPIO16-Pad4)") (class "Default")
      (node (ref "ESP1") (pin "4") (pinfunction "GPIO16_4") (pintype "passive"))
    )
    (net (code "83") (name "unconnected-(SD*1-CD_SW-Pad9)") (class "Default")
      (node (ref "SD*1") (pin "9") (pinfunction "CD_SW_9") (pintype "passive+no_connect"))
    )
    (net (code "84") (name "unconnected-(SD*1-Pad10)") (class "Default")
      (node (ref "SD*1") (pin "10") (pinfunction "10_10") (pintype "passive+no_connect"))
    )
    (net (code "85") (name "unconnected-(SD*1-Pad11)") (class "Default")
      (node (ref "SD*1") (pin "11") (pinfunction "11_11") (pintype "passive+no_connect"))
    )
    (net (code "86") (name "unconnected-(SD*1-Pad12)") (class "Default")
      (node (ref "SD*1") (pin "12") (pinfunction "12_12") (pintype "passive+no_connect"))
    )
    (net (code "87") (name "unconnected-(SD*1-Pad13)") (class "Default")
      (node (ref "SD*1") (pin "13") (pinfunction "13_13") (pintype "passive+no_connect"))
    )
    (net (code "88") (name "unconnected-(U2-CTS#-Pad9)") (class "Default")
      (node (ref "U2") (pin "9") (pinfunction "CTS#_9") (pintype "passive+no_connect"))
    )
    (net (code "89") (name "unconnected-(U2-DCD#-Pad12)") (class "Default")
      (node (ref "U2") (pin "12") (pinfunction "DCD#_12") (pintype "passive+no_connect"))
    )
    (net (code "90") (name "unconnected-(U2-DSR#-Pad10)") (class "Default")
      (node (ref "U2") (pin "10") (pinfunction "DSR#_10") (pintype "passive+no_connect"))
    )
    (net (code "91") (name "unconnected-(U2-DTR#-Pad13)") (class "Default")
      (node (ref "U2") (pin "13") (pinfunction "DTR#_13") (pintype "passive+no_connect"))
    )
    (net (code "92") (name "unconnected-(U2-R232-Pad15)") (class "Default")
      (node (ref "U2") (pin "15") (pinfunction "R232_15") (pintype "passive+no_connect"))
    )
    (net (code "93") (name "unconnected-(U2-RI#-Pad11)") (class "Default")
      (node (ref "U2") (pin "11") (pinfunction "RI#_11") (pintype "passive+no_connect"))
    )
    (net (code "94") (name "unconnected-(U2-RTS#-Pad14)") (class "Default")
      (node (ref "U2") (pin "14") (pinfunction "RTS#_14") (pintype "passive+no_connect"))
    )
    (net (code "95") (name "unconnected-(U4-NC-Pad9)") (class "Default")
      (node (ref "U4") (pin "9") (pinfunction "NC_9") (pintype "passive"))
    )
    (net (code "96") (name "unconnected-(U6A-PA0-WKUP-Pad14)") (class "Default")
      (node (ref "U6") (pin "14") (pinfunction "PA0-WKUP_14") (pintype "bidirectional"))
    )
    (net (code "97") (name "unconnected-(U6A-PA8-Pad41)") (class "Default")
      (node (ref "U6") (pin "41") (pinfunction "PA8_41") (pintype "bidirectional"))
    )
    (net (code "98") (name "unconnected-(U6A-PA11-Pad44)") (class "Default")
      (node (ref "U6") (pin "44") (pinfunction "PA11_44") (pintype "bidirectional"))
    )
    (net (code "99") (name "unconnected-(U6A-PA12-Pad45)") (class "Default")
      (node (ref "U6") (pin "45") (pinfunction "PA12_45") (pintype "bidirectional"))
    )
    (net (code "100") (name "unconnected-(U6A-PB0-Pad26)") (class "Default")
      (node (ref "U6") (pin "26") (pinfunction "PB0_26") (pintype "bidirectional"))
    )
    (net (code "101") (name "unconnected-(U6A-PB1-Pad27)") (class "Default")
      (node (ref "U6") (pin "27") (pinfunction "PB1_27") (pintype "bidirectional"))
    )
    (net (code "102") (name "unconnected-(U6A-PB8-Pad61)") (class "Default")
      (node (ref "U6") (pin "61") (pinfunction "PB8_61") (pintype "bidirectional"))
    )
    (net (code "103") (name "unconnected-(U6A-PB9-Pad62)") (class "Default")
      (node (ref "U6") (pin "62") (pinfunction "PB9_62") (pintype "bidirectional"))
    )
    (net (code "104") (name "unconnected-(U6A-PB12-Pad33)") (class "Default")
      (node (ref "U6") (pin "33") (pinfunction "PB12_33") (pintype "bidirectional"))
    )
    (net (code "105") (name "unconnected-(U6A-PB13-Pad34)") (class "Default")
      (node (ref "U6") (pin "34") (pinfunction "PB13_34") (pintype "bidirectional"))
    )
    (net (code "106") (name "unconnected-(U6A-PB14-Pad35)") (class "Default")
      (node (ref "U6") (pin "35") (pinfunction "PB14_35") (pintype "bidirectional"))
    )
    (net (code "107") (name "unconnected-(U6A-PB15-Pad36)") (class "Default")
      (node (ref "U6") (pin "36") (pinfunction "PB15_36") (pintype "bidirectional"))
    )
    (net (code "108") (name "unconnected-(U6A-PC0-Pad8)") (class "Default")
      (node (ref "U6") (pin "8") (pinfunction "PC0_8") (pintype "bidirectional"))
    )
    (net (code "109") (name "unconnected-(U6A-PC1-Pad9)") (class "Default")
      (node (ref "U6") (pin "9") (pinfunction "PC1_9") (pintype "bidirectional"))
    )
    (net (code "110") (name "unconnected-(U6A-PC2-Pad10)") (class "Default")
      (node (ref "U6") (pin "10") (pinfunction "PC2_10") (pintype "bidirectional"))
    )
    (net (code "111") (name "unconnected-(U6A-PC3-Pad11)") (class "Default")
      (node (ref "U6") (pin "11") (pinfunction "PC3_11") (pintype "bidirectional"))
    )
    (net (code "112") (name "unconnected-(U6A-PC5-Pad25)") (class "Default")
      (node (ref "U6") (pin "25") (pinfunction "PC5_25") (pintype "bidirectional"))
    )
    (net (code "113") (name "unconnected-(U6A-PC6-Pad37)") (class "Default")
      (node (ref "U6") (pin "37") (pinfunction "PC6_37") (pintype "bidirectional"))
    )
    (net (code "114") (name "unconnected-(U6A-PC7-Pad38)") (class "Default")
      (node (ref "U6") (pin "38") (pinfunction "PC7_38") (pintype "bidirectional"))
    )
    (net (code "115") (name "unconnected-(U6A-PC13-TAMPER-RTC-Pad2)") (class "Default")
      (node (ref "U6") (pin "2") (pinfunction "PC13-TAMPER-RTC_2") (pintype "bidirectional"))
    )
    (net (code "116") (name "unconnected-(USB1-ID-Pad4)") (class "Default")
      (node (ref "USB1") (pin "4") (pinfunction "ID_4") (pintype "passive+no_connect"))
    )
    (net (code "117") (name "unconnected-(USB1-Shield-Pad0)") (class "Default")
      (node (ref "USB1") (pin "0") (pinfunction "Shield_0") (pintype "passive"))
    )
  )
)
